# connect.net
KiCad netlist of a schematic drawn in Altium Designer
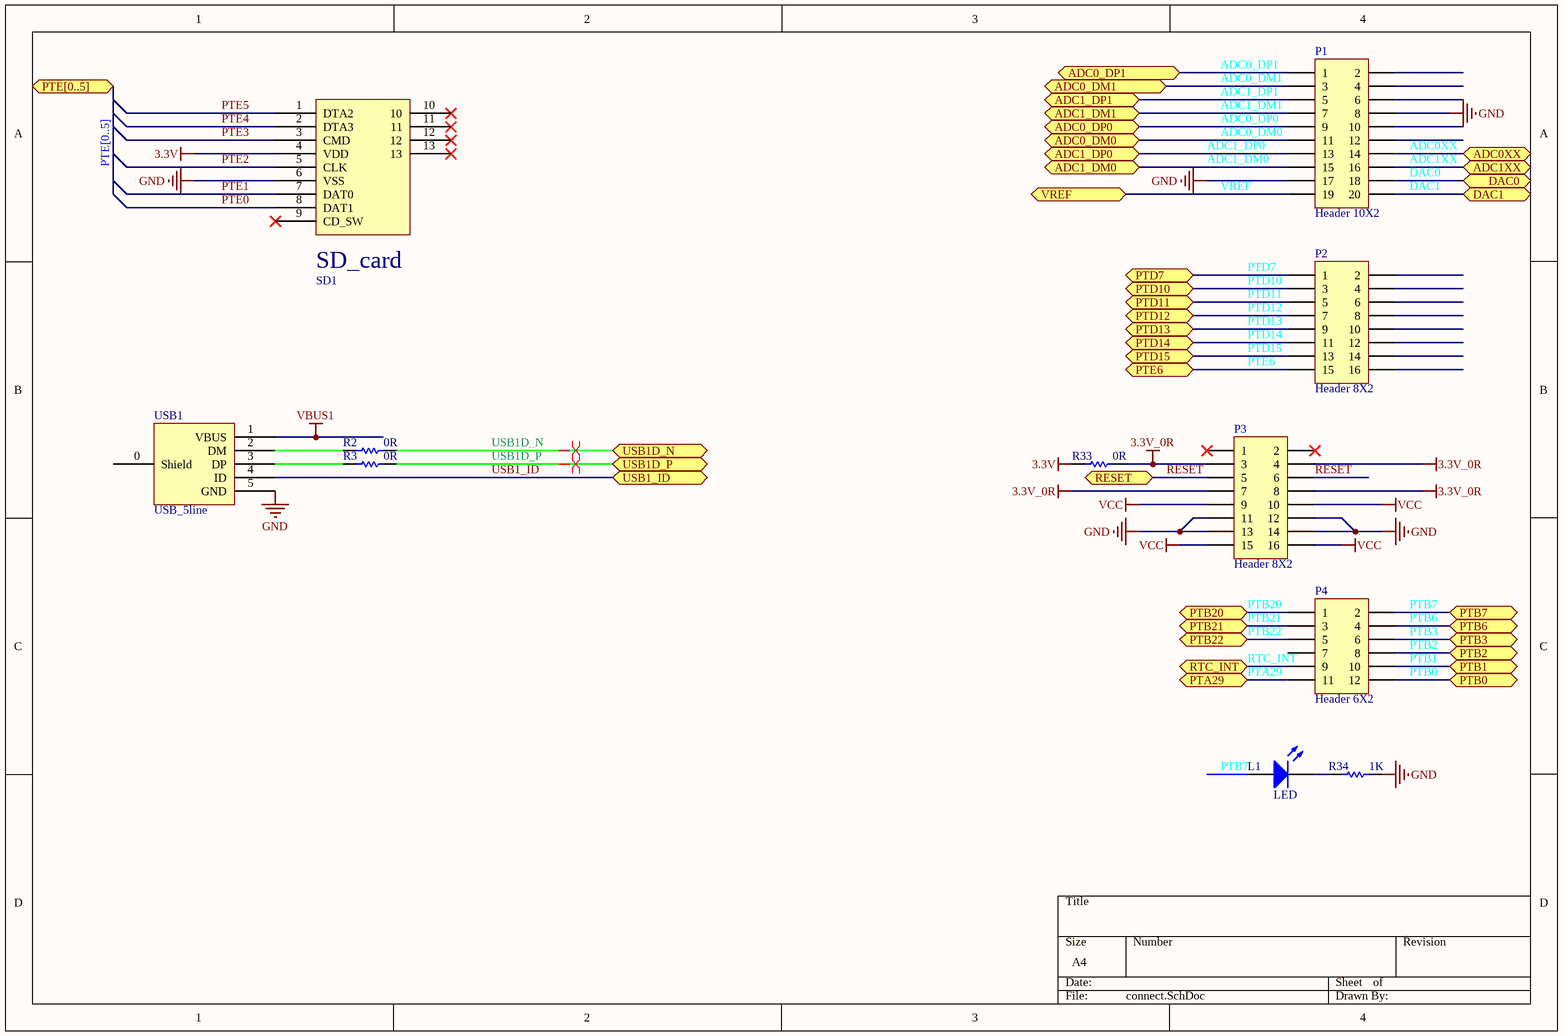
[diagram p0: connect.SchDoc]

(export (version "E")
  (design (tool "Eeschema 10.0.6"))
  (components
    (comp (ref "L1") (value "LED") (footprint "1608[0603]") (libsource (lib "Sparks") (part "LED")))
    (comp (ref "P1")
      (value "Header 10X2")
      (footprint "HDR2X10")
      (description "Header, 10-Pin, Dual row")
      (fields (field (name "PUBLISHER") "Altium Limited"))
      (libsource (lib "Sparks") (part "Header 10X2"))
    )
    (comp (ref "P2")
      (value "Header 8X2")
      (footprint "HDR2X8")
      (description "Header, 8-Pin, Dual row")
      (fields (field (name "PUBLISHER") "Altium Limited"))
      (libsource (lib "Sparks") (part "Header 8X2"))
    )
    (comp (ref "P3")
      (value "Header 8X2")
      (footprint "HDR2X8")
      (description "Header, 8-Pin, Dual row")
      (fields (field (name "PUBLISHER") "Altium Limited"))
      (libsource (lib "Sparks") (part "Header 8X2"))
    )
    (comp (ref "P4")
      (value "Header 6X2")
      (footprint "HDR2X6")
      (description "Header, 6-Pin, Dual row")
      (fields (field (name "PUBLISHER") "Altium Limited"))
      (libsource (lib "Sparks") (part "Header 6X2"))
    )
    (comp (ref "R2")
      (value "0R")
      (footprint "1608[0603]")
      (description "贴片电阻")
      (fields (field (name "Comment") "Res") (field (name "PUBLISHER") "Altium Limited"))
      (libsource (lib "Sparks") (part "Res"))
    )
    (comp (ref "R3")
      (value "0R")
      (footprint "1608[0603]")
      (description "贴片电阻")
      (fields (field (name "Comment") "Res") (field (name "PUBLISHER") "Altium Limited"))
      (libsource (lib "Sparks") (part "Res"))
    )
    (comp (ref "R33")
      (value "0R")
      (footprint "1206")
      (description "贴片电阻")
      (fields (field (name "Comment") "Res") (field (name "PUBLISHER") "Altium Limited"))
      (libsource (lib "Sparks") (part "Res"))
    )
    (comp (ref "R34")
      (value "1K")
      (footprint "1608[0603]")
      (description "贴片电阻")
      (fields (field (name "Comment") "Res") (field (name "PUBLISHER") "Altium Limited"))
      (libsource (lib "Sparks") (part "Res"))
    )
    (comp (ref "SD1") (value "TF_card") (footprint "TF卡座(短体)") (libsource (lib "2号库") (part "TF_card")))
    (comp (ref "USB1")
      (value "USB_5line")
      (footprint "USB-MICRO-5P-2F")
      (libsource (lib "2号库") (part "USB_5line"))
    )
  )
  (nets
    (net (code "1") (name "/ADC0XX") (class "Default")
      (node (ref "P1") (pin "14") (pinfunction "14_14") (pintype "passive"))
    )
    (net (code "2") (name "/ADC0_DM0") (class "Default")
      (node (ref "P1") (pin "11") (pinfunction "11_11") (pintype "passive"))
    )
    (net (code "3") (name "/ADC0_DM1") (class "Default")
      (node (ref "P1") (pin "3") (pinfunction "3_3") (pintype "passive"))
    )
    (net (code "4") (name "/ADC0_DP0") (class "Default")
      (node (ref "P1") (pin "9") (pinfunction "9_9") (pintype "passive"))
    )
    (net (code "5") (name "/ADC0_DP1") (class "Default")
      (node (ref "P1") (pin "1") (pinfunction "1_1") (pintype "passive"))
    )
    (net (code "6") (name "/ADC1XX") (class "Default")
      (node (ref "P1") (pin "16") (pinfunction "16_16") (pintype "passive"))
    )
    (net (code "7") (name "/ADC1_DM0") (class "Default")
      (node (ref "P1") (pin "15") (pinfunction "15_15") (pintype "passive"))
    )
    (net (code "8") (name "/ADC1_DM1") (class "Default")
      (node (ref "P1") (pin "7") (pinfunction "7_7") (pintype "passive"))
    )
    (net (code "9") (name "/ADC1_DP0") (class "Default")
      (node (ref "P1") (pin "13") (pinfunction "13_13") (pintype "passive"))
    )
    (net (code "10") (name "/ADC1_DP1") (class "Default")
      (node (ref "P1") (pin "5") (pinfunction "5_5") (pintype "passive"))
    )
    (net (code "11") (name "/DAC0") (class "Default")
      (node (ref "P1") (pin "18") (pinfunction "18_18") (pintype "passive"))
    )
    (net (code "12") (name "/DAC1") (class "Default")
      (node (ref "P1") (pin "20") (pinfunction "20_20") (pintype "passive"))
    )
    (net (code "13") (name "/PTA29") (class "Default")
      (node (ref "P4") (pin "11") (pinfunction "11_11") (pintype "passive"))
    )
    (net (code "14") (name "/PTB0") (class "Default")
      (node (ref "P4") (pin "12") (pinfunction "12_12") (pintype "passive"))
    )
    (net (code "15") (name "/PTB1") (class "Default")
      (node (ref "P4") (pin "10") (pinfunction "10_10") (pintype "passive"))
    )
    (net (code "16") (name "/PTB2") (class "Default")
      (node (ref "P4") (pin "8") (pinfunction "8_8") (pintype "passive"))
    )
    (net (code "17") (name "/PTB3") (class "Default")
      (node (ref "P4") (pin "6") (pinfunction "6_6") (pintype "passive"))
    )
    (net (code "18") (name "/PTB6") (class "Default")
      (node (ref "P4") (pin "4") (pinfunction "4_4") (pintype "passive"))
    )
    (net (code "19") (name "/PTB7") (class "Default")
      (node (ref "L1") (pin "1") (pinfunction "A_1") (pintype "passive"))
      (node (ref "P4") (pin "2") (pinfunction "2_2") (pintype "passive"))
    )
    (net (code "20") (name "/PTB20") (class "Default")
      (node (ref "P4") (pin "1") (pinfunction "1_1") (pintype "passive"))
    )
    (net (code "21") (name "/PTB21") (class "Default")
      (node (ref "P4") (pin "3") (pinfunction "3_3") (pintype "passive"))
    )
    (net (code "22") (name "/PTB22") (class "Default")
      (node (ref "P4") (pin "5") (pinfunction "5_5") (pintype "passive"))
    )
    (net (code "23") (name "/PTD7") (class "Default")
      (node (ref "P2") (pin "1") (pinfunction "1_1") (pintype "passive"))
    )
    (net (code "24") (name "/PTD10") (class "Default")
      (node (ref "P2") (pin "3") (pinfunction "3_3") (pintype "passive"))
    )
    (net (code "25") (name "/PTD11") (class "Default")
      (node (ref "P2") (pin "5") (pinfunction "5_5") (pintype "passive"))
    )
    (net (code "26") (name "/PTD12") (class "Default")
      (node (ref "P2") (pin "7") (pinfunction "7_7") (pintype "passive"))
    )
    (net (code "27") (name "/PTD13") (class "Default")
      (node (ref "P2") (pin "9") (pinfunction "9_9") (pintype "passive"))
    )
    (net (code "28") (name "/PTD14") (class "Default")
      (node (ref "P2") (pin "11") (pinfunction "11_11") (pintype "passive"))
    )
    (net (code "29") (name "/PTD15") (class "Default")
      (node (ref "P2") (pin "13") (pinfunction "13_13") (pintype "passive"))
    )
    (net (code "30") (name "/PTE0") (class "Default")
      (node (ref "SD1") (pin "8") (pinfunction "DAT1_8") (pintype "passive"))
    )
    (net (code "31") (name "/PTE1") (class "Default")
      (node (ref "SD1") (pin "7") (pinfunction "DAT0_7") (pintype "passive"))
    )
    (net (code "32") (name "/PTE2") (class "Default")
      (node (ref "SD1") (pin "5") (pinfunction "CLK_5") (pintype "passive"))
    )
    (net (code "33") (name "/PTE3") (class "Default")
      (node (ref "SD1") (pin "3") (pinfunction "CMD_3") (pintype "passive"))
    )
    (net (code "34") (name "/PTE4") (class "Default")
      (node (ref "SD1") (pin "2") (pinfunction "DTA3_2") (pintype "passive"))
    )
    (net (code "35") (name "/PTE5") (class "Default")
      (node (ref "SD1") (pin "1") (pinfunction "DTA2_1") (pintype "passive"))
    )
    (net (code "36") (name "/PTE6") (class "Default")
      (node (ref "P2") (pin "15") (pinfunction "15_15") (pintype "passive"))
    )
    (net (code "38") (name "/RESET") (class "Default")
      (node (ref "P3") (pin "5") (pinfunction "5_5") (pintype "passive"))
      (node (ref "P3") (pin "6") (pinfunction "6_6") (pintype "passive"))
    )
    (net (code "39") (name "/RTC_INT") (class "Default")
      (node (ref "P4") (pin "9") (pinfunction "9_9") (pintype "passive"))
    )
    (net (code "40") (name "/USB1D_N") (class "Default")
      (node (ref "R2") (pin "1") (pinfunction "1_1") (pintype "passive"))
    )
    (net (code "41") (name "/USB1D_P") (class "Default")
      (node (ref "R3") (pin "1") (pinfunction "1_1") (pintype "passive"))
    )
    (net (code "42") (name "/USB1_ID") (class "Default")
      (node (ref "USB1") (pin "4") (pinfunction "ID_4") (pintype "passive"))
    )
    (net (code "43") (name "/VREF") (class "Default")
      (node (ref "P1") (pin "19") (pinfunction "19_19") (pintype "passive"))
    )
    (net (code "44") (name "3.3V") (class "Default")
      (node (ref "R33") (pin "2") (pinfunction "2_2") (pintype "passive"))
      (node (ref "SD1") (pin "4") (pinfunction "VDD_4") (pintype "passive"))
    )
    (net (code "45") (name "3.3V_0R") (class "Default")
      (node (ref "P3") (pin "3") (pinfunction "3_3") (pintype "passive"))
      (node (ref "P3") (pin "4") (pinfunction "4_4") (pintype "passive"))
      (node (ref "P3") (pin "7") (pinfunction "7_7") (pintype "passive"))
      (node (ref "P3") (pin "8") (pinfunction "8_8") (pintype "passive"))
      (node (ref "R33") (pin "1") (pinfunction "1_1") (pintype "passive"))
    )
    (net (code "46") (name "GND") (class "Default")
      (node (ref "P1") (pin "17") (pinfunction "17_17") (pintype "passive"))
      (node (ref "P1") (pin "8") (pinfunction "8_8") (pintype "passive"))
      (node (ref "P3") (pin "11") (pinfunction "11_11") (pintype "passive"))
      (node (ref "P3") (pin "12") (pinfunction "12_12") (pintype "passive"))
      (node (ref "P3") (pin "13") (pinfunction "13_13") (pintype "passive"))
      (node (ref "P3") (pin "14") (pinfunction "14_14") (pintype "passive"))
      (node (ref "R34") (pin "1") (pinfunction "1_1") (pintype "passive"))
      (node (ref "SD1") (pin "6") (pinfunction "VSS_6") (pintype "passive"))
      (node (ref "USB1") (pin "5") (pinfunction "GND_5") (pintype "passive"))
    )
    (net (code "47") (name "Net-(L1-K)") (class "Default")
      (node (ref "L1") (pin "2") (pinfunction "K_2") (pintype "passive"))
      (node (ref "R34") (pin "2") (pinfunction "2_2") (pintype "passive"))
    )
    (net (code "48") (name "Net-(USB1-DM)") (class "Default")
      (node (ref "R2") (pin "2") (pinfunction "2_2") (pintype "passive"))
      (node (ref "USB1") (pin "2") (pinfunction "DM_2") (pintype "passive"))
    )
    (net (code "49") (name "Net-(USB1-DP)") (class "Default")
      (node (ref "R3") (pin "2") (pinfunction "2_2") (pintype "passive"))
      (node (ref "USB1") (pin "3") (pinfunction "DP_3") (pintype "passive"))
    )
    (net (code "50") (name "VBUS1") (class "Default")
      (node (ref "USB1") (pin "1") (pinfunction "VBUS_1") (pintype "passive"))
    )
    (net (code "51") (name "VCC") (class "Default")
      (node (ref "P3") (pin "10") (pinfunction "10_10") (pintype "passive"))
      (node (ref "P3") (pin "15") (pinfunction "15_15") (pintype "passive"))
      (node (ref "P3") (pin "16") (pinfunction "16_16") (pintype "passive"))
      (node (ref "P3") (pin "9") (pinfunction "9_9") (pintype "passive"))
    )
    (net (code "52") (name "unconnected-(P1-Pad2)") (class "Default")
      (node (ref "P1") (pin "2") (pinfunction "2_2") (pintype "passive"))
    )
    (net (code "53") (name "unconnected-(P1-Pad4)") (class "Default")
      (node (ref "P1") (pin "4") (pinfunction "4_4") (pintype "passive"))
    )
    (net (code "54") (name "unconnected-(P1-Pad6)") (class "Default")
      (node (ref "P1") (pin "6") (pinfunction "6_6") (pintype "passive"))
    )
    (net (code "55") (name "unconnected-(P1-Pad10)") (class "Default")
      (node (ref "P1") (pin "10") (pinfunction "10_10") (pintype "passive"))
    )
    (net (code "56") (name "unconnected-(P1-Pad12)") (class "Default")
      (node (ref "P1") (pin "12") (pinfunction "12_12") (pintype "passive"))
    )
    (net (code "57") (name "unconnected-(P2-Pad2)") (class "Default")
      (node (ref "P2") (pin "2") (pinfunction "2_2") (pintype "passive"))
    )
    (net (code "58") (name "unconnected-(P2-Pad4)") (class "Default")
      (node (ref "P2") (pin "4") (pinfunction "4_4") (pintype "passive"))
    )
    (net (code "59") (name "unconnected-(P2-Pad6)") (class "Default")
      (node (ref "P2") (pin "6") (pinfunction "6_6") (pintype "passive"))
    )
    (net (code "60") (name "unconnected-(P2-Pad8)") (class "Default")
      (node (ref "P2") (pin "8") (pinfunction "8_8") (pintype "passive"))
    )
    (net (code "61") (name "unconnected-(P2-Pad10)") (class "Default")
      (node (ref "P2") (pin "10") (pinfunction "10_10") (pintype "passive"))
    )
    (net (code "62") (name "unconnected-(P2-Pad12)") (class "Default")
      (node (ref "P2") (pin "12") (pinfunction "12_12") (pintype "passive"))
    )
    (net (code "63") (name "unconnected-(P2-Pad14)") (class "Default")
      (node (ref "P2") (pin "14") (pinfunction "14_14") (pintype "passive"))
    )
    (net (code "64") (name "unconnected-(P2-Pad16)") (class "Default")
      (node (ref "P2") (pin "16") (pinfunction "16_16") (pintype "passive"))
    )
    (net (code "65") (name "unconnected-(P3-Pad1)") (class "Default")
      (node (ref "P3") (pin "1") (pinfunction "1_1") (pintype "passive+no_connect"))
    )
    (net (code "66") (name "unconnected-(P3-Pad2)") (class "Default")
      (node (ref "P3") (pin "2") (pinfunction "2_2") (pintype "passive+no_connect"))
    )
    (net (code "67") (name "unconnected-(P4-Pad7)") (class "Default")
      (node (ref "P4") (pin "7") (pinfunction "7_7") (pintype "passive"))
    )
    (net (code "68") (name "unconnected-(SD1-CD_SW-Pad9)") (class "Default")
      (node (ref "SD1") (pin "9") (pinfunction "CD_SW_9") (pintype "passive+no_connect"))
    )
    (net (code "69") (name "unconnected-(SD1-Pad10)") (class "Default")
      (node (ref "SD1") (pin "10") (pinfunction "10_10") (pintype "passive+no_connect"))
    )
    (net (code "70") (name "unconnected-(SD1-Pad11)") (class "Default")
      (node (ref "SD1") (pin "11") (pinfunction "11_11") (pintype "passive+no_connect"))
    )
    (net (code "71") (name "unconnected-(SD1-Pad12)") (class "Default")
      (node (ref "SD1") (pin "12") (pinfunction "12_12") (pintype "passive+no_connect"))
    )
    (net (code "72") (name "unconnected-(SD1-Pad13)") (class "Default")
      (node (ref "SD1") (pin "13") (pinfunction "13_13") (pintype "passive+no_connect"))
    )
    (net (code "73") (name "unconnected-(USB1-Shield-Pad0)") (class "Default")
      (node (ref "USB1") (pin "0") (pinfunction "Shield_0") (pintype "passive"))
    )
  )
)
